# hp_pcb_easyeda_std.net
KiCad netlist of a schematic drawn in EasyEDA
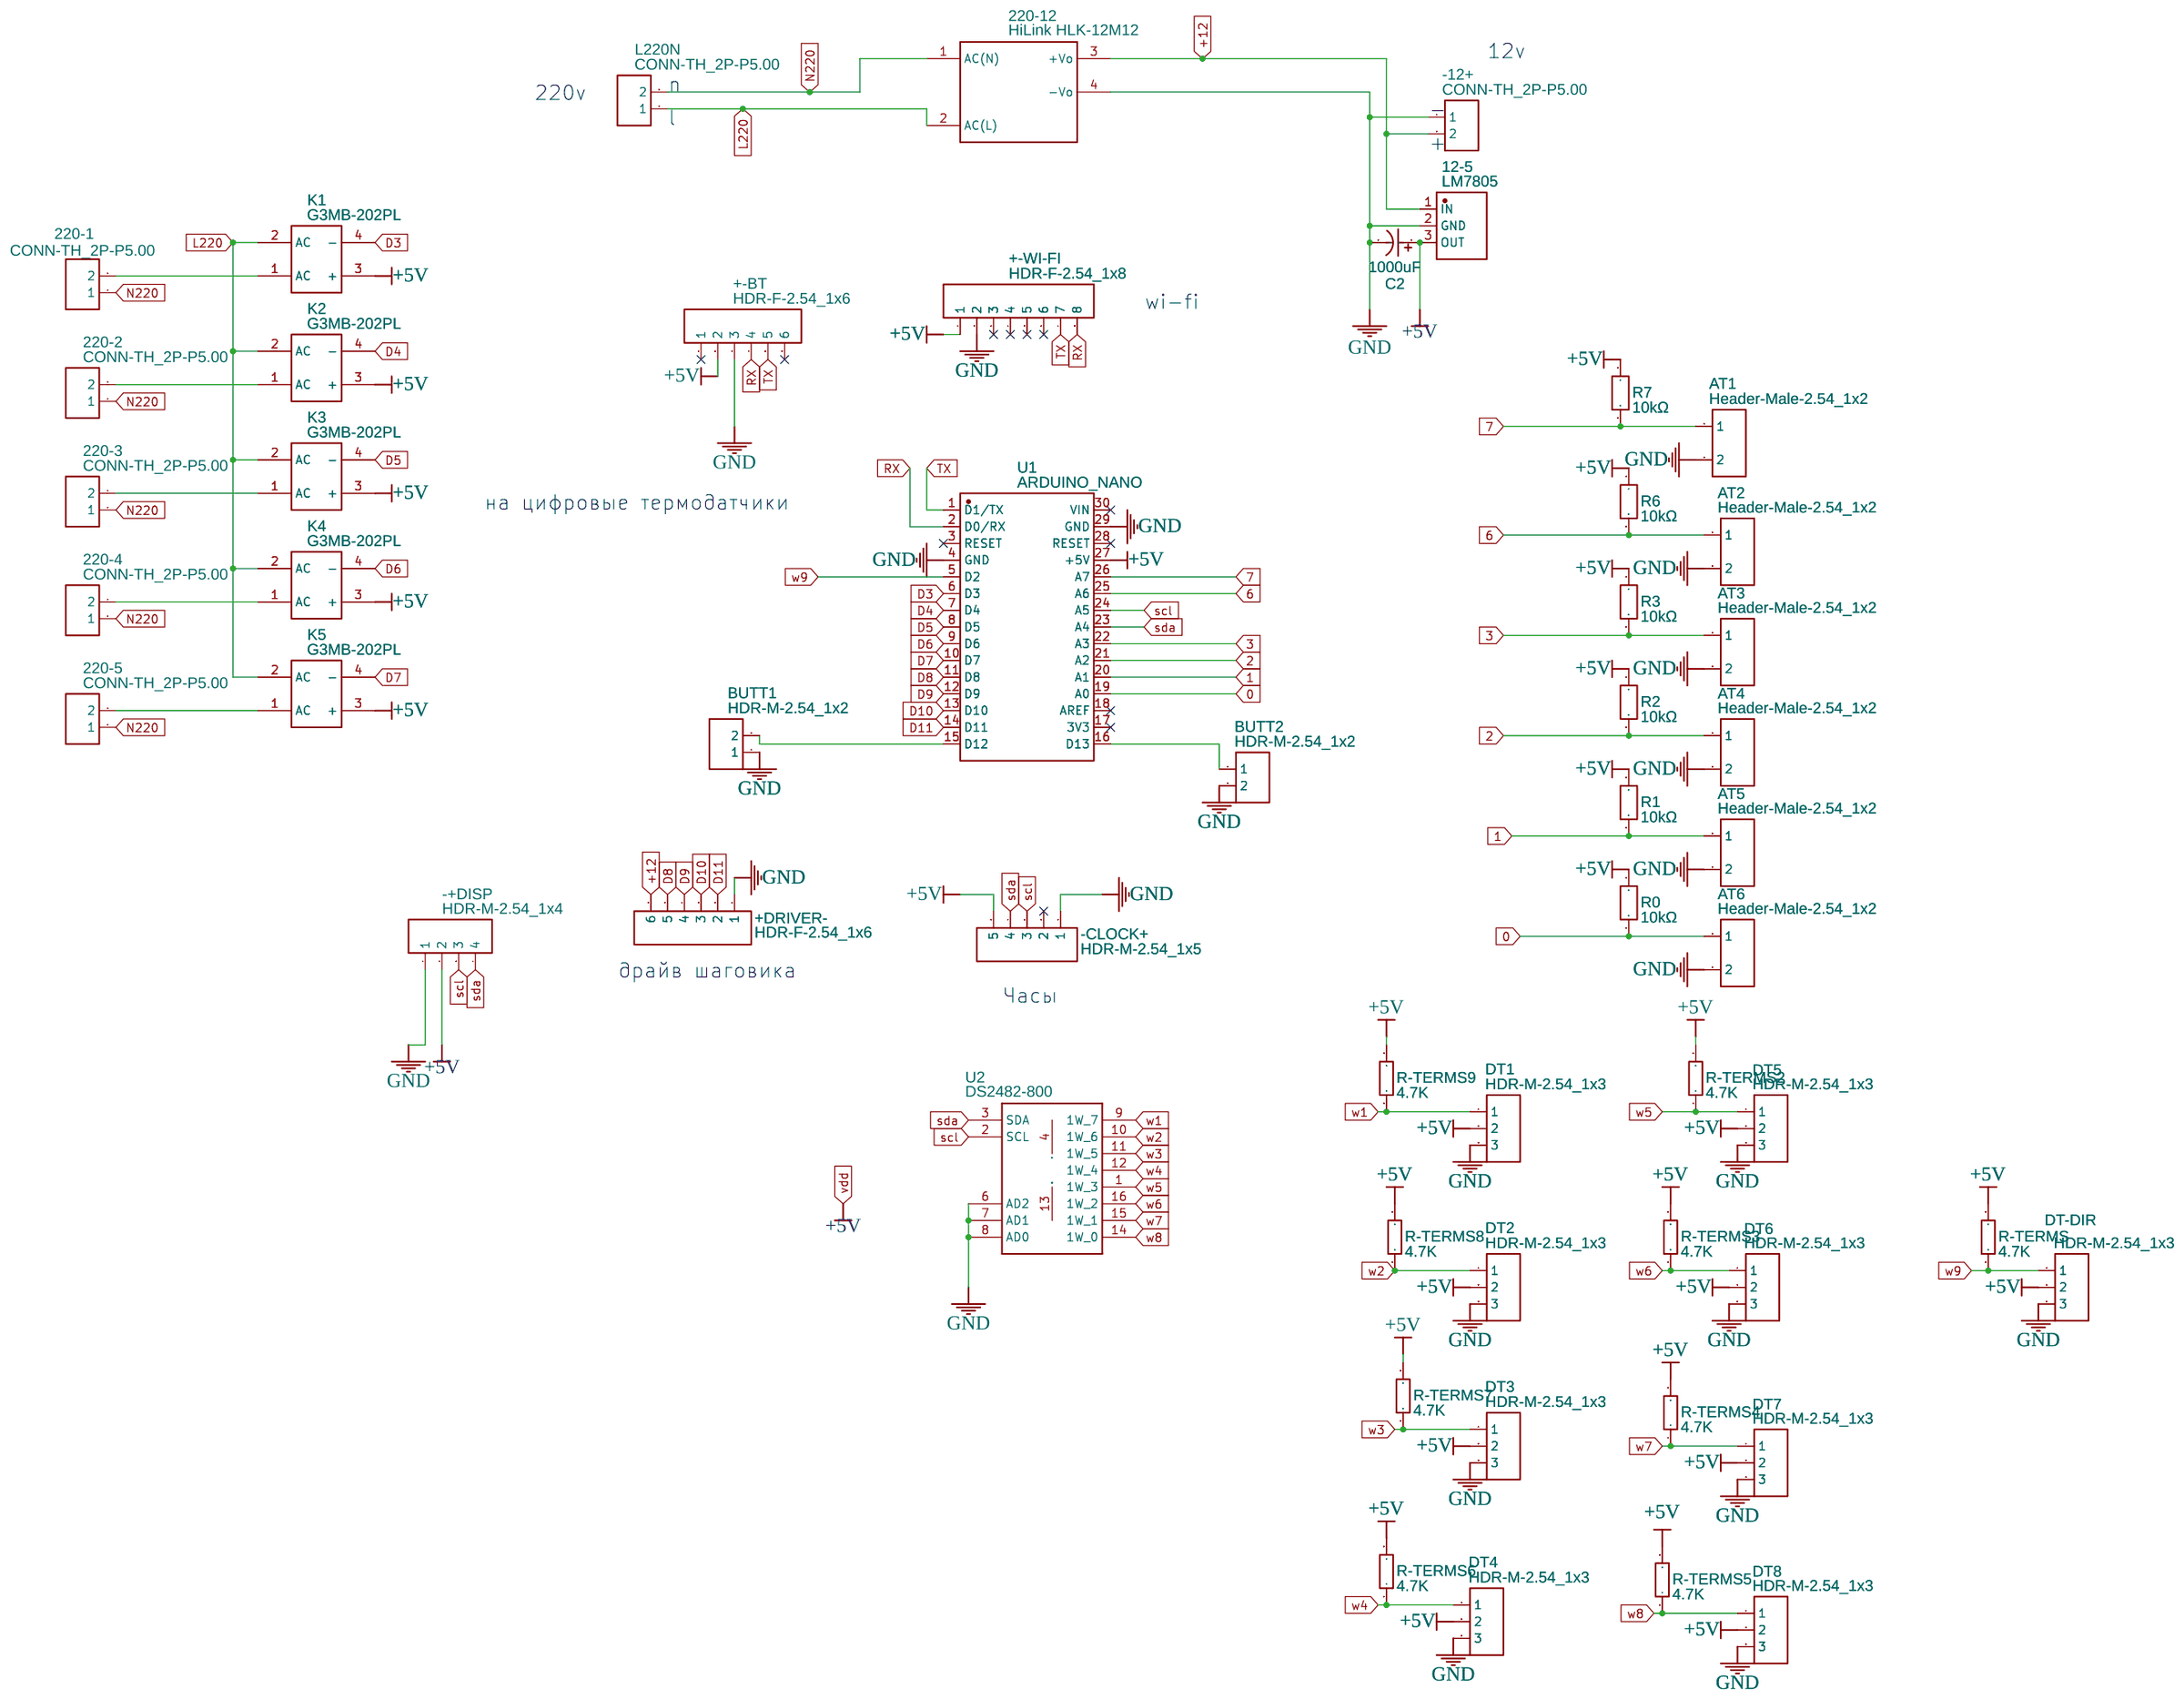
[diagram p0: schematic sheet]

(export (version "E")
  (design (tool "Eeschema 10.0.6"))
  (components
    (comp (ref "+-BT") (value "HDR-F-2.54_1x6") (libsource (lib "") (part "HDR-F-2.54_1x6")))
    (comp (ref "+-WI-FI") (value "HDR-F-2.54_1x8") (libsource (lib "") (part "HDR-F-2.54_1x8")))
    (comp (ref "+DRIVER-") (value "HDR-F-2.54_1x6") (libsource (lib "") (part "HDR-F-2.54_1x6_1")))
    (comp (ref "-+DISP") (value "HDR-M-2.54_1x4") (libsource (lib "") (part "HDR-M-2.54_1x4")))
    (comp (ref "-12+") (value "CONN-TH_2P-P5.00") (libsource (lib "") (part "CONN-TH_2P-P5.00_2")))
    (comp (ref "-CLOCK+") (value "HDR-M-2.54_1x5") (libsource (lib "") (part "HDR-M-2.54_1x5")))
    (comp (ref "12-5")
      (value "LM7805")
      (fields (field (name "Manufacturer") "TF"))
      (libsource (lib "") (part "LM7805"))
    )
    (comp (ref "220-1") (value "CONN-TH_2P-P5.00") (libsource (lib "") (part "CONN-TH_2P-P5.00_1")))
    (comp (ref "220-2") (value "CONN-TH_2P-P5.00") (libsource (lib "") (part "CONN-TH_2P-P5.00_1")))
    (comp (ref "220-3") (value "CONN-TH_2P-P5.00") (libsource (lib "") (part "CONN-TH_2P-P5.00_1")))
    (comp (ref "220-4") (value "CONN-TH_2P-P5.00") (libsource (lib "") (part "CONN-TH_2P-P5.00_1")))
    (comp (ref "220-5") (value "CONN-TH_2P-P5.00") (libsource (lib "") (part "CONN-TH_2P-P5.00_1")))
    (comp (ref "220-12")
      (value "HiLink HLK-12M12")
      (fields (field (name "Manufacturer Part") "HLK-12M12") (field (name "Manufacturer") "HiLink"))
      (libsource (lib "") (part "HiLink HLK-12M12"))
    )
    (comp (ref "AT1")
      (value "Header-Male-2.54_1x2")
      (fields
        (field (name "Manufacturer Part") "826629-2")
        (field (name "Manufacturer") "TE Connectivity(美国泰科)")
      )
      (libsource (lib "") (part "Header-Male-2.54_1x2"))
    )
    (comp (ref "AT2")
      (value "Header-Male-2.54_1x2")
      (fields
        (field (name "Manufacturer Part") "826629-2")
        (field (name "Manufacturer") "TE Connectivity(美国泰科)")
      )
      (libsource (lib "") (part "Header-Male-2.54_1x2"))
    )
    (comp (ref "AT3")
      (value "Header-Male-2.54_1x2")
      (fields
        (field (name "Manufacturer Part") "826629-2")
        (field (name "Manufacturer") "TE Connectivity(美国泰科)")
      )
      (libsource (lib "") (part "Header-Male-2.54_1x2"))
    )
    (comp (ref "AT4")
      (value "Header-Male-2.54_1x2")
      (fields
        (field (name "Manufacturer Part") "826629-2")
        (field (name "Manufacturer") "TE Connectivity(美国泰科)")
      )
      (libsource (lib "") (part "Header-Male-2.54_1x2"))
    )
    (comp (ref "AT5")
      (value "Header-Male-2.54_1x2")
      (fields
        (field (name "Manufacturer Part") "826629-2")
        (field (name "Manufacturer") "TE Connectivity(美国泰科)")
      )
      (libsource (lib "") (part "Header-Male-2.54_1x2"))
    )
    (comp (ref "AT6")
      (value "Header-Male-2.54_1x2")
      (fields
        (field (name "Manufacturer Part") "826629-2")
        (field (name "Manufacturer") "TE Connectivity(美国泰科)")
      )
      (libsource (lib "") (part "Header-Male-2.54_1x2"))
    )
    (comp (ref "BUTT1") (value "HDR-M-2.54_1x2") (libsource (lib "") (part "HDR-M-2.54_1x2_1")))
    (comp (ref "BUTT2") (value "HDR-M-2.54_1x2") (libsource (lib "") (part "HDR-M-2.54_1x2")))
    (comp (ref "C2")
      (value "1000uF")
      (fields (field (name "Manufacturer Part") "1000uF 10V绿金 8*14") (field (name "Manufacturer") "ValuePro"))
      (libsource (lib "") (part "1000uF 10V 8*14"))
    )
    (comp (ref "DT-DIR") (value "HDR-M-2.54_1x3") (libsource (lib "") (part "HDR-M-2.54_1x3_1")))
    (comp (ref "DT1") (value "HDR-M-2.54_1x3") (libsource (lib "") (part "HDR-M-2.54_1x3")))
    (comp (ref "DT2") (value "HDR-M-2.54_1x3") (libsource (lib "") (part "HDR-M-2.54_1x3")))
    (comp (ref "DT3") (value "HDR-M-2.54_1x3") (libsource (lib "") (part "HDR-M-2.54_1x3")))
    (comp (ref "DT4") (value "HDR-M-2.54_1x3") (libsource (lib "") (part "HDR-M-2.54_1x3")))
    (comp (ref "DT5") (value "HDR-M-2.54_1x3") (libsource (lib "") (part "HDR-M-2.54_1x3")))
    (comp (ref "DT6") (value "HDR-M-2.54_1x3") (libsource (lib "") (part "HDR-M-2.54_1x3")))
    (comp (ref "DT7") (value "HDR-M-2.54_1x3") (libsource (lib "") (part "HDR-M-2.54_1x3")))
    (comp (ref "DT8") (value "HDR-M-2.54_1x3") (libsource (lib "") (part "HDR-M-2.54_1x3")))
    (comp (ref "K1")
      (value "G3MB-202PL")
      (fields (field (name "Manufacturer") "OMRON(欧姆龙)"))
      (libsource (lib "") (part "G3MB-202PL"))
    )
    (comp (ref "K2")
      (value "G3MB-202PL")
      (fields (field (name "Manufacturer") "OMRON(欧姆龙)"))
      (libsource (lib "") (part "G3MB-202PL"))
    )
    (comp (ref "K3")
      (value "G3MB-202PL")
      (fields (field (name "Manufacturer") "OMRON(欧姆龙)"))
      (libsource (lib "") (part "G3MB-202PL"))
    )
    (comp (ref "K4")
      (value "G3MB-202PL")
      (fields (field (name "Manufacturer") "OMRON(欧姆龙)"))
      (libsource (lib "") (part "G3MB-202PL"))
    )
    (comp (ref "K5")
      (value "G3MB-202PL")
      (fields (field (name "Manufacturer") "OMRON(欧姆龙)"))
      (libsource (lib "") (part "G3MB-202PL"))
    )
    (comp (ref "L220N") (value "CONN-TH_2P-P5.00") (libsource (lib "") (part "CONN-TH_2P-P5.00")))
    (comp (ref "R-TERMS")
      (value "4.7K")
      (fields (field (name "Manufacturer") "Chian Chia Elec"))
      (libsource (lib "") (part "CF1/4W-4.7KΩ±5% T52"))
    )
    (comp (ref "R-TERMS2")
      (value "4.7K")
      (fields (field (name "Manufacturer") "Chian Chia Elec"))
      (libsource (lib "") (part "CF1/4W-4.7KΩ±5% T52"))
    )
    (comp (ref "R-TERMS3")
      (value "4.7K")
      (fields (field (name "Manufacturer") "Chian Chia Elec"))
      (libsource (lib "") (part "CF1/4W-4.7KΩ±5% T52"))
    )
    (comp (ref "R-TERMS4")
      (value "4.7K")
      (fields (field (name "Manufacturer") "Chian Chia Elec"))
      (libsource (lib "") (part "CF1/4W-4.7KΩ±5% T52"))
    )
    (comp (ref "R-TERMS5")
      (value "4.7K")
      (fields (field (name "Manufacturer") "Chian Chia Elec"))
      (libsource (lib "") (part "CF1/4W-4.7KΩ±5% T52"))
    )
    (comp (ref "R-TERMS6")
      (value "4.7K")
      (fields (field (name "Manufacturer") "Chian Chia Elec"))
      (libsource (lib "") (part "CF1/4W-4.7KΩ±5% T52"))
    )
    (comp (ref "R-TERMS7")
      (value "4.7K")
      (fields (field (name "Manufacturer") "Chian Chia Elec"))
      (libsource (lib "") (part "CF1/4W-4.7KΩ±5% T52"))
    )
    (comp (ref "R-TERMS8")
      (value "4.7K")
      (fields (field (name "Manufacturer") "Chian Chia Elec"))
      (libsource (lib "") (part "CF1/4W-4.7KΩ±5% T52"))
    )
    (comp (ref "R-TERMS9")
      (value "4.7K")
      (fields (field (name "Manufacturer") "Chian Chia Elec"))
      (libsource (lib "") (part "CF1/4W-4.7KΩ±5% T52"))
    )
    (comp (ref "R0")
      (value "10kΩ")
      (fields (field (name "Manufacturer Part") "MF1/8W-10KΩ±1%T52") (field (name "Manufacturer") "华星机电"))
      (libsource (lib "") (part "MF1/8W-10KΩ±1%T52"))
    )
    (comp (ref "R1")
      (value "10kΩ")
      (fields (field (name "Manufacturer Part") "MF1/8W-10KΩ±1%T52") (field (name "Manufacturer") "华星机电"))
      (libsource (lib "") (part "MF1/8W-10KΩ±1%T52"))
    )
    (comp (ref "R2")
      (value "10kΩ")
      (fields (field (name "Manufacturer Part") "MF1/8W-10KΩ±1%T52") (field (name "Manufacturer") "华星机电"))
      (libsource (lib "") (part "MF1/8W-10KΩ±1%T52"))
    )
    (comp (ref "R3")
      (value "10kΩ")
      (fields (field (name "Manufacturer Part") "MF1/8W-10KΩ±1%T52") (field (name "Manufacturer") "华星机电"))
      (libsource (lib "") (part "MF1/8W-10KΩ±1%T52"))
    )
    (comp (ref "R6")
      (value "10kΩ")
      (fields (field (name "Manufacturer Part") "MF1/8W-10KΩ±1%T52") (field (name "Manufacturer") "华星机电"))
      (libsource (lib "") (part "MF1/8W-10KΩ±1%T52"))
    )
    (comp (ref "R7")
      (value "10kΩ")
      (fields (field (name "Manufacturer Part") "MF1/8W-10KΩ±1%T52") (field (name "Manufacturer") "华星机电"))
      (libsource (lib "") (part "MF1/8W-10KΩ±1%T52"))
    )
    (comp (ref "U1") (value "ARDUINO_NANO") (libsource (lib "") (part "ARDUINO_NANO")))
    (comp (ref "U2") (value "DS2482-800") (libsource (lib "") (part "DS2482-800")))
  )
  (nets
    (net (code "1") (name "+12") (class "Default")
      (node (ref "+DRIVER-") (pin "6") (pinfunction "6_6") (pintype "input"))
      (node (ref "-12+") (pin "2") (pinfunction "2_2") (pintype "unspecified"))
      (node (ref "12-5") (pin "1") (pinfunction "IN_1") (pintype "unspecified"))
      (node (ref "220-12") (pin "3") (pinfunction "+Vo_3") (pintype "unspecified"))
    )
    (net (code "2") (name "0") (class "Default")
      (node (ref "AT6") (pin "1") (pinfunction "1_1") (pintype "unspecified"))
      (node (ref "R0") (pin "2") (pinfunction "2_2") (pintype "unspecified"))
      (node (ref "U1") (pin "19") (pinfunction "A0_19") (pintype "unspecified"))
    )
    (net (code "3") (name "1") (class "Default")
      (node (ref "AT5") (pin "1") (pinfunction "1_1") (pintype "unspecified"))
      (node (ref "R1") (pin "2") (pinfunction "2_2") (pintype "unspecified"))
      (node (ref "U1") (pin "20") (pinfunction "A1_20") (pintype "unspecified"))
    )
    (net (code "4") (name "2") (class "Default")
      (node (ref "AT4") (pin "1") (pinfunction "1_1") (pintype "unspecified"))
      (node (ref "R2") (pin "2") (pinfunction "2_2") (pintype "unspecified"))
      (node (ref "U1") (pin "21") (pinfunction "A2_21") (pintype "unspecified"))
    )
    (net (code "5") (name "3") (class "Default")
      (node (ref "AT3") (pin "1") (pinfunction "1_1") (pintype "unspecified"))
      (node (ref "R3") (pin "2") (pinfunction "2_2") (pintype "unspecified"))
      (node (ref "U1") (pin "22") (pinfunction "A3_22") (pintype "unspecified"))
    )
    (net (code "6") (name "6") (class "Default")
      (node (ref "AT2") (pin "1") (pinfunction "1_1") (pintype "unspecified"))
      (node (ref "R6") (pin "2") (pinfunction "2_2") (pintype "unspecified"))
      (node (ref "U1") (pin "25") (pinfunction "A6_25") (pintype "unspecified"))
    )
    (net (code "7") (name "7") (class "Default")
      (node (ref "AT1") (pin "1") (pinfunction "1_1") (pintype "unspecified"))
      (node (ref "R7") (pin "2") (pinfunction "2_2") (pintype "unspecified"))
      (node (ref "U1") (pin "26") (pinfunction "A7_26") (pintype "unspecified"))
    )
    (net (code "8") (name "D3") (class "Default")
      (node (ref "K1") (pin "4") (pinfunction "-_4") (pintype "unspecified"))
      (node (ref "U1") (pin "6") (pinfunction "D3_6") (pintype "unspecified"))
    )
    (net (code "9") (name "D4") (class "Default")
      (node (ref "K2") (pin "4") (pinfunction "-_4") (pintype "unspecified"))
      (node (ref "U1") (pin "7") (pinfunction "D4_7") (pintype "unspecified"))
    )
    (net (code "10") (name "D5") (class "Default")
      (node (ref "K3") (pin "4") (pinfunction "-_4") (pintype "unspecified"))
      (node (ref "U1") (pin "8") (pinfunction "D5_8") (pintype "unspecified"))
    )
    (net (code "11") (name "D6") (class "Default")
      (node (ref "K4") (pin "4") (pinfunction "-_4") (pintype "unspecified"))
      (node (ref "U1") (pin "9") (pinfunction "D6_9") (pintype "unspecified"))
    )
    (net (code "12") (name "D7") (class "Default")
      (node (ref "K5") (pin "4") (pinfunction "-_4") (pintype "unspecified"))
      (node (ref "U1") (pin "10") (pinfunction "D7_10") (pintype "unspecified"))
    )
    (net (code "13") (name "D8") (class "Default")
      (node (ref "+DRIVER-") (pin "5") (pinfunction "5_5") (pintype "input"))
      (node (ref "U1") (pin "11") (pinfunction "D8_11") (pintype "unspecified"))
    )
    (net (code "14") (name "D9") (class "Default")
      (node (ref "+DRIVER-") (pin "4") (pinfunction "4_4") (pintype "input"))
      (node (ref "U1") (pin "12") (pinfunction "D9_12") (pintype "unspecified"))
    )
    (net (code "15") (name "D10") (class "Default")
      (node (ref "+DRIVER-") (pin "3") (pinfunction "3_3") (pintype "input"))
      (node (ref "U1") (pin "13") (pinfunction "D10_13") (pintype "unspecified"))
    )
    (net (code "16") (name "D11") (class "Default")
      (node (ref "+DRIVER-") (pin "2") (pinfunction "2_2") (pintype "input"))
      (node (ref "U1") (pin "14") (pinfunction "D11_14") (pintype "unspecified"))
    )
    (net (code "17") (name "GND") (class "Default")
      (node (ref "+-BT") (pin "3") (pinfunction "3_3") (pintype "input"))
      (node (ref "+-WI-FI") (pin "2") (pinfunction "2_2") (pintype "unspecified"))
      (node (ref "+DRIVER-") (pin "1") (pinfunction "1_1") (pintype "input"))
      (node (ref "-+DISP") (pin "1") (pinfunction "1_1") (pintype "unspecified"))
      (node (ref "-12+") (pin "1") (pinfunction "1_1") (pintype "unspecified"))
      (node (ref "-CLOCK+") (pin "1") (pinfunction "1_1") (pintype "unspecified"))
      (node (ref "12-5") (pin "2") (pinfunction "GND_2") (pintype "unspecified"))
      (node (ref "220-12") (pin "4") (pinfunction "-Vo_4") (pintype "unspecified"))
      (node (ref "AT1") (pin "2") (pinfunction "2_2") (pintype "unspecified"))
      (node (ref "AT2") (pin "2") (pinfunction "2_2") (pintype "unspecified"))
      (node (ref "AT3") (pin "2") (pinfunction "2_2") (pintype "unspecified"))
      (node (ref "AT4") (pin "2") (pinfunction "2_2") (pintype "unspecified"))
      (node (ref "AT5") (pin "2") (pinfunction "2_2") (pintype "unspecified"))
      (node (ref "AT6") (pin "2") (pinfunction "2_2") (pintype "unspecified"))
      (node (ref "BUTT1") (pin "1") (pinfunction "1_1") (pintype "unspecified"))
      (node (ref "BUTT2") (pin "2") (pinfunction "2_2") (pintype "unspecified"))
      (node (ref "C2") (pin "2") (pinfunction "2_2") (pintype "input"))
      (node (ref "DT-DIR") (pin "3") (pinfunction "3_3") (pintype "input"))
      (node (ref "DT1") (pin "3") (pinfunction "3_3") (pintype "input"))
      (node (ref "DT2") (pin "3") (pinfunction "3_3") (pintype "input"))
      (node (ref "DT3") (pin "3") (pinfunction "3_3") (pintype "input"))
      (node (ref "DT4") (pin "3") (pinfunction "3_3") (pintype "input"))
      (node (ref "DT5") (pin "3") (pinfunction "3_3") (pintype "input"))
      (node (ref "DT6") (pin "3") (pinfunction "3_3") (pintype "input"))
      (node (ref "DT7") (pin "3") (pinfunction "3_3") (pintype "input"))
      (node (ref "DT8") (pin "3") (pinfunction "3_3") (pintype "input"))
      (node (ref "U1") (pin "29") (pinfunction "GND_29") (pintype "unspecified"))
      (node (ref "U1") (pin "4") (pinfunction "GND_4") (pintype "unspecified"))
      (node (ref "U2") (pin "6") (pinfunction "AD2_6") (pintype "input"))
      (node (ref "U2") (pin "7") (pinfunction "AD1_7") (pintype "input"))
      (node (ref "U2") (pin "8") (pinfunction "AD0_8") (pintype "input"))
    )
    (net (code "18") (name "L220") (class "Default")
      (node (ref "220-12") (pin "2") (pinfunction "AC(L)_2") (pintype "unspecified"))
      (node (ref "K1") (pin "2") (pinfunction "AC_2") (pintype "unspecified"))
      (node (ref "K2") (pin "2") (pinfunction "AC_2") (pintype "unspecified"))
      (node (ref "K3") (pin "2") (pinfunction "AC_2") (pintype "unspecified"))
      (node (ref "K4") (pin "2") (pinfunction "AC_2") (pintype "unspecified"))
      (node (ref "K5") (pin "2") (pinfunction "AC_2") (pintype "unspecified"))
      (node (ref "L220N") (pin "1") (pinfunction "1_1") (pintype "unspecified"))
    )
    (net (code "19") (name "N220") (class "Default")
      (node (ref "220-1") (pin "1") (pinfunction "1_1") (pintype "unspecified"))
      (node (ref "220-12") (pin "1") (pinfunction "AC(N)_1") (pintype "unspecified"))
      (node (ref "220-2") (pin "1") (pinfunction "1_1") (pintype "unspecified"))
      (node (ref "220-3") (pin "1") (pinfunction "1_1") (pintype "unspecified"))
      (node (ref "220-4") (pin "1") (pinfunction "1_1") (pintype "unspecified"))
      (node (ref "220-5") (pin "1") (pinfunction "1_1") (pintype "unspecified"))
      (node (ref "L220N") (pin "2") (pinfunction "2_2") (pintype "unspecified"))
    )
    (net (code "20") (name "Net-(220-1-Pad2)") (class "Default")
      (node (ref "220-1") (pin "2") (pinfunction "2_2") (pintype "unspecified"))
      (node (ref "K1") (pin "1") (pinfunction "AC_1") (pintype "unspecified"))
    )
    (net (code "21") (name "Net-(220-2-Pad2)") (class "Default")
      (node (ref "220-2") (pin "2") (pinfunction "2_2") (pintype "unspecified"))
      (node (ref "K2") (pin "1") (pinfunction "AC_1") (pintype "unspecified"))
    )
    (net (code "22") (name "Net-(220-3-Pad2)") (class "Default")
      (node (ref "220-3") (pin "2") (pinfunction "2_2") (pintype "unspecified"))
      (node (ref "K3") (pin "1") (pinfunction "AC_1") (pintype "unspecified"))
    )
    (net (code "23") (name "Net-(220-4-Pad2)") (class "Default")
      (node (ref "220-4") (pin "2") (pinfunction "2_2") (pintype "unspecified"))
      (node (ref "K4") (pin "1") (pinfunction "AC_1") (pintype "unspecified"))
    )
    (net (code "24") (name "Net-(220-5-Pad2)") (class "Default")
      (node (ref "220-5") (pin "2") (pinfunction "2_2") (pintype "unspecified"))
      (node (ref "K5") (pin "1") (pinfunction "AC_1") (pintype "unspecified"))
    )
    (net (code "25") (name "Net-(U1-D12)") (class "Default")
      (node (ref "BUTT1") (pin "2") (pinfunction "2_2") (pintype "unspecified"))
      (node (ref "U1") (pin "15") (pinfunction "D12_15") (pintype "unspecified"))
    )
    (net (code "26") (name "Net-(U1-D13)") (class "Default")
      (node (ref "BUTT2") (pin "1") (pinfunction "1_1") (pintype "unspecified"))
      (node (ref "U1") (pin "16") (pinfunction "D13_16") (pintype "unspecified"))
    )
    (net (code "27") (name "RX") (class "Default")
      (node (ref "+-BT") (pin "4") (pinfunction "4_4") (pintype "input"))
      (node (ref "+-WI-FI") (pin "8") (pinfunction "8_8") (pintype "unspecified"))
      (node (ref "U1") (pin "2") (pinfunction "D0/RX_2") (pintype "unspecified"))
    )
    (net (code "28") (name "TX") (class "Default")
      (node (ref "+-BT") (pin "5") (pinfunction "5_5") (pintype "input"))
      (node (ref "+-WI-FI") (pin "7") (pinfunction "7_7") (pintype "unspecified"))
      (node (ref "U1") (pin "1") (pinfunction "D1/TX_1") (pintype "unspecified"))
    )
    (net (code "29") (name "scl") (class "Default")
      (node (ref "-+DISP") (pin "3") (pinfunction "3_3") (pintype "unspecified"))
      (node (ref "-CLOCK+") (pin "3") (pinfunction "3_3") (pintype "unspecified"))
      (node (ref "U1") (pin "24") (pinfunction "A5_24") (pintype "unspecified"))
      (node (ref "U2") (pin "2") (pinfunction "SCL_2") (pintype "input"))
    )
    (net (code "30") (name "sda") (class "Default")
      (node (ref "-+DISP") (pin "4") (pinfunction "4_4") (pintype "unspecified"))
      (node (ref "-CLOCK+") (pin "4") (pinfunction "4_4") (pintype "unspecified"))
      (node (ref "U1") (pin "23") (pinfunction "A4_23") (pintype "unspecified"))
      (node (ref "U2") (pin "3") (pinfunction "SDA_3") (pintype "unspecified"))
    )
    (net (code "31") (name "unconnected-(+-BT-Pad1)") (class "Default")
      (node (ref "+-BT") (pin "1") (pinfunction "1_1") (pintype "input+no_connect"))
    )
    (net (code "32") (name "unconnected-(+-BT-Pad6)") (class "Default")
      (node (ref "+-BT") (pin "6") (pinfunction "6_6") (pintype "input+no_connect"))
    )
    (net (code "33") (name "unconnected-(+-WI-FI-Pad3)") (class "Default")
      (node (ref "+-WI-FI") (pin "3") (pinfunction "3_3") (pintype "unspecified+no_connect"))
    )
    (net (code "34") (name "unconnected-(+-WI-FI-Pad4)") (class "Default")
      (node (ref "+-WI-FI") (pin "4") (pinfunction "4_4") (pintype "unspecified+no_connect"))
    )
    (net (code "35") (name "unconnected-(+-WI-FI-Pad5)") (class "Default")
      (node (ref "+-WI-FI") (pin "5") (pinfunction "5_5") (pintype "unspecified+no_connect"))
    )
    (net (code "36") (name "unconnected-(+-WI-FI-Pad6)") (class "Default")
      (node (ref "+-WI-FI") (pin "6") (pinfunction "6_6") (pintype "unspecified+no_connect"))
    )
    (net (code "37") (name "unconnected-(-CLOCK+-Pad2)") (class "Default")
      (node (ref "-CLOCK+") (pin "2") (pinfunction "2_2") (pintype "unspecified+no_connect"))
    )
    (net (code "38") (name "unconnected-(U1-3V3-Pad17)") (class "Default")
      (node (ref "U1") (pin "17") (pinfunction "3V3_17") (pintype "unspecified+no_connect"))
    )
    (net (code "39") (name "unconnected-(U1-AREF-Pad18)") (class "Default")
      (node (ref "U1") (pin "18") (pinfunction "AREF_18") (pintype "unspecified+no_connect"))
    )
    (net (code "40") (name "unconnected-(U1-RESET-Pad3)") (class "Default")
      (node (ref "U1") (pin "3") (pinfunction "RESET_3") (pintype "unspecified+no_connect"))
    )
    (net (code "41") (name "unconnected-(U1-RESET-Pad28)") (class "Default")
      (node (ref "U1") (pin "28") (pinfunction "RESET_28") (pintype "unspecified+no_connect"))
    )
    (net (code "42") (name "unconnected-(U1-VIN-Pad30)") (class "Default")
      (node (ref "U1") (pin "30") (pinfunction "VIN_30") (pintype "unspecified+no_connect"))
    )
    (net (code "43") (name "unconnected-(U2-GND-Pad13)") (class "Default")
      (node (ref "U2") (pin "13") (pinfunction "GND_13") (pintype "passive"))
    )
    (net (code "44") (name "unconnected-(U2-VDD-Pad4)") (class "Default")
      (node (ref "U2") (pin "4") (pinfunction "VDD_4") (pintype "passive"))
    )
    (net (code "45") (name "vdd") (class "Default")
      (node (ref "+-BT") (pin "2") (pinfunction "2_2") (pintype "input"))
      (node (ref "+-WI-FI") (pin "1") (pinfunction "1_1") (pintype "unspecified"))
      (node (ref "-+DISP") (pin "2") (pinfunction "2_2") (pintype "unspecified"))
      (node (ref "-CLOCK+") (pin "5") (pinfunction "5_5") (pintype "unspecified"))
      (node (ref "12-5") (pin "3") (pinfunction "OUT_3") (pintype "unspecified"))
      (node (ref "C2") (pin "1") (pinfunction "1_1") (pintype "input"))
      (node (ref "DT-DIR") (pin "2") (pinfunction "2_2") (pintype "input"))
      (node (ref "DT1") (pin "2") (pinfunction "2_2") (pintype "input"))
      (node (ref "DT2") (pin "2") (pinfunction "2_2") (pintype "input"))
      (node (ref "DT3") (pin "2") (pinfunction "2_2") (pintype "input"))
      (node (ref "DT4") (pin "2") (pinfunction "2_2") (pintype "input"))
      (node (ref "DT5") (pin "2") (pinfunction "2_2") (pintype "input"))
      (node (ref "DT6") (pin "2") (pinfunction "2_2") (pintype "input"))
      (node (ref "DT7") (pin "2") (pinfunction "2_2") (pintype "input"))
      (node (ref "DT8") (pin "2") (pinfunction "2_2") (pintype "input"))
      (node (ref "K1") (pin "3") (pinfunction "+_3") (pintype "unspecified"))
      (node (ref "K2") (pin "3") (pinfunction "+_3") (pintype "unspecified"))
      (node (ref "K3") (pin "3") (pinfunction "+_3") (pintype "unspecified"))
      (node (ref "K4") (pin "3") (pinfunction "+_3") (pintype "unspecified"))
      (node (ref "K5") (pin "3") (pinfunction "+_3") (pintype "unspecified"))
      (node (ref "R-TERMS") (pin "2") (pinfunction "2_2") (pintype "unspecified"))
      (node (ref "R-TERMS2") (pin "2") (pinfunction "2_2") (pintype "unspecified"))
      (node (ref "R-TERMS3") (pin "2") (pinfunction "2_2") (pintype "unspecified"))
      (node (ref "R-TERMS4") (pin "2") (pinfunction "2_2") (pintype "unspecified"))
      (node (ref "R-TERMS5") (pin "2") (pinfunction "2_2") (pintype "unspecified"))
      (node (ref "R-TERMS6") (pin "2") (pinfunction "2_2") (pintype "unspecified"))
      (node (ref "R-TERMS7") (pin "2") (pinfunction "2_2") (pintype "unspecified"))
      (node (ref "R-TERMS8") (pin "2") (pinfunction "2_2") (pintype "unspecified"))
      (node (ref "R-TERMS9") (pin "2") (pinfunction "2_2") (pintype "unspecified"))
      (node (ref "R0") (pin "1") (pinfunction "1_1") (pintype "unspecified"))
      (node (ref "R1") (pin "1") (pinfunction "1_1") (pintype "unspecified"))
      (node (ref "R2") (pin "1") (pinfunction "1_1") (pintype "unspecified"))
      (node (ref "R3") (pin "1") (pinfunction "1_1") (pintype "unspecified"))
      (node (ref "R6") (pin "1") (pinfunction "1_1") (pintype "unspecified"))
      (node (ref "R7") (pin "1") (pinfunction "1_1") (pintype "unspecified"))
      (node (ref "U1") (pin "27") (pinfunction "+5V_27") (pintype "unspecified"))
    )
    (net (code "46") (name "w1") (class "Default")
      (node (ref "DT1") (pin "1") (pinfunction "1_1") (pintype "input"))
      (node (ref "R-TERMS9") (pin "1") (pinfunction "1_1") (pintype "unspecified"))
      (node (ref "U2") (pin "9") (pinfunction "1W_7_9") (pintype "unspecified"))
    )
    (net (code "47") (name "w2") (class "Default")
      (node (ref "DT2") (pin "1") (pinfunction "1_1") (pintype "input"))
      (node (ref "R-TERMS8") (pin "1") (pinfunction "1_1") (pintype "unspecified"))
      (node (ref "U2") (pin "10") (pinfunction "1W_6_10") (pintype "unspecified"))
    )
    (net (code "48") (name "w3") (class "Default")
      (node (ref "DT3") (pin "1") (pinfunction "1_1") (pintype "input"))
      (node (ref "R-TERMS7") (pin "1") (pinfunction "1_1") (pintype "unspecified"))
      (node (ref "U2") (pin "11") (pinfunction "1W_5_11") (pintype "unspecified"))
    )
    (net (code "49") (name "w4") (class "Default")
      (node (ref "DT4") (pin "1") (pinfunction "1_1") (pintype "input"))
      (node (ref "R-TERMS6") (pin "1") (pinfunction "1_1") (pintype "unspecified"))
      (node (ref "U2") (pin "12") (pinfunction "1W_4_12") (pintype "unspecified"))
    )
    (net (code "50") (name "w5") (class "Default")
      (node (ref "DT5") (pin "1") (pinfunction "1_1") (pintype "input"))
      (node (ref "R-TERMS2") (pin "1") (pinfunction "1_1") (pintype "unspecified"))
      (node (ref "U2") (pin "1") (pinfunction "1W_3_1") (pintype "unspecified"))
    )
    (net (code "51") (name "w6") (class "Default")
      (node (ref "DT6") (pin "1") (pinfunction "1_1") (pintype "input"))
      (node (ref "R-TERMS3") (pin "1") (pinfunction "1_1") (pintype "unspecified"))
      (node (ref "U2") (pin "16") (pinfunction "1W_2_16") (pintype "unspecified"))
    )
    (net (code "52") (name "w7") (class "Default")
      (node (ref "DT7") (pin "1") (pinfunction "1_1") (pintype "input"))
      (node (ref "R-TERMS4") (pin "1") (pinfunction "1_1") (pintype "unspecified"))
      (node (ref "U2") (pin "15") (pinfunction "1W_1_15") (pintype "unspecified"))
    )
    (net (code "53") (name "w8") (class "Default")
      (node (ref "DT8") (pin "1") (pinfunction "1_1") (pintype "input"))
      (node (ref "R-TERMS5") (pin "1") (pinfunction "1_1") (pintype "unspecified"))
      (node (ref "U2") (pin "14") (pinfunction "1W_0_14") (pintype "unspecified"))
    )
    (net (code "54") (name "w9") (class "Default")
      (node (ref "DT-DIR") (pin "1") (pinfunction "1_1") (pintype "input"))
      (node (ref "R-TERMS") (pin "1") (pinfunction "1_1") (pintype "unspecified"))
      (node (ref "U1") (pin "5") (pinfunction "D2_5") (pintype "unspecified"))
    )
  )
)
